# HOME_AUTOMATION.net
KiCad netlist of a schematic drawn in EAGLE
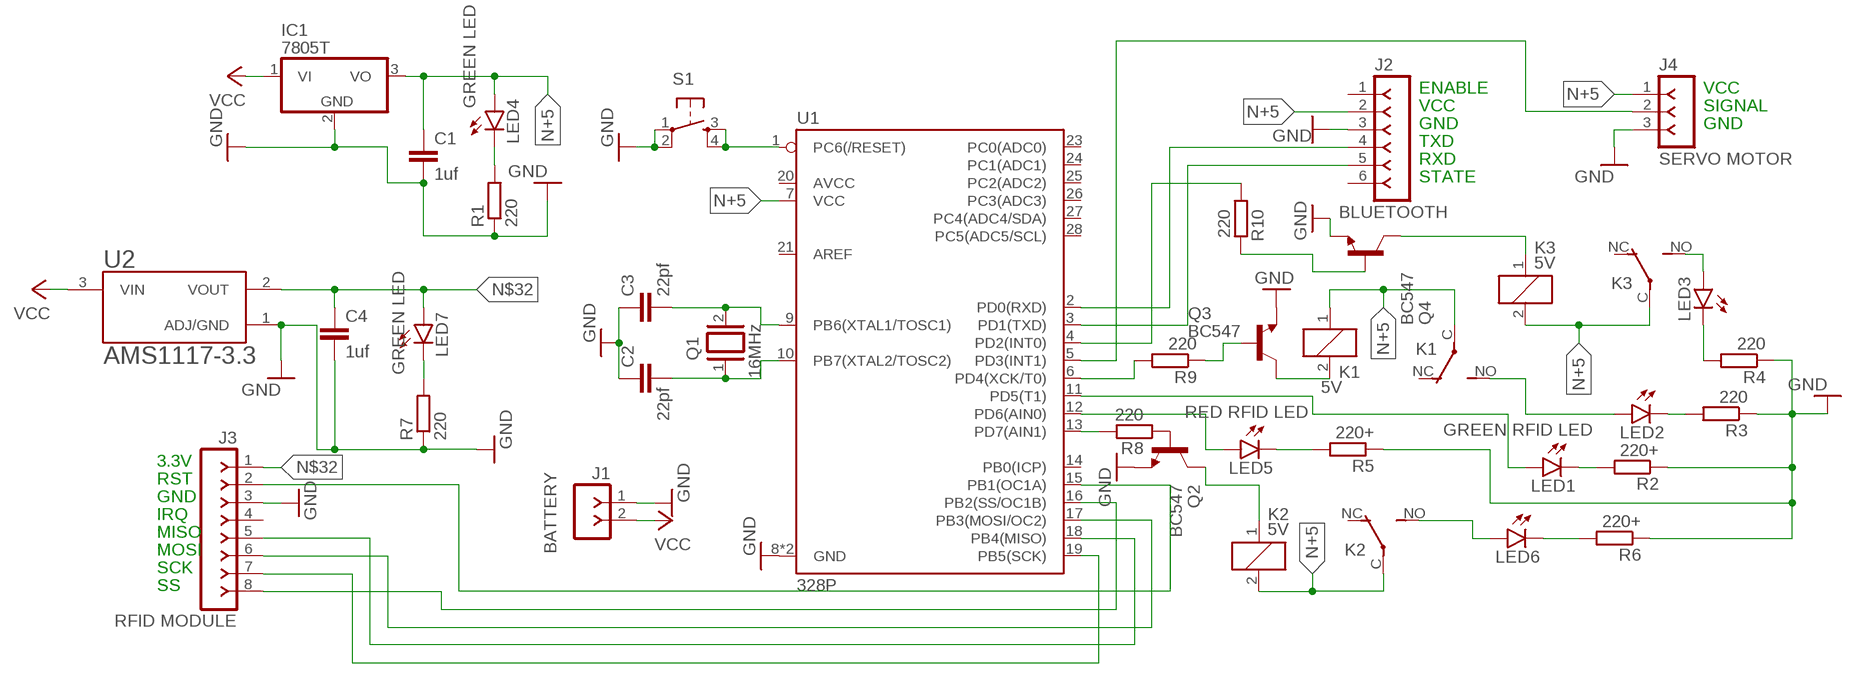
[diagram p0: schematic, sheet 1]

(export (version "E")
  (design (tool "Eeschema 10.0.6"))
  (components
    (comp (ref "C1")
      (value "1uf")
      (footprint "eagle-import:C025-025X050")
      (libsource (lib "eagle-import") (part "C-EU025-025X050"))
    )
    (comp (ref "C2")
      (value "22pf")
      (footprint "eagle-import:C025-025X050")
      (libsource (lib "eagle-import") (part "C-EU025-025X050"))
    )
    (comp (ref "C3")
      (value "22pf")
      (footprint "eagle-import:C025-025X050")
      (libsource (lib "eagle-import") (part "C-EU025-025X050"))
    )
    (comp (ref "C4")
      (value "1uf")
      (footprint "eagle-import:C025-025X050")
      (libsource (lib "eagle-import") (part "C-EU025-025X050"))
    )
    (comp (ref "IC1")
      (value "7805T")
      (footprint "eagle-import:TO220H")
      (libsource (lib "eagle-import") (part "78T05"))
    )
    (comp (ref "J1")
      (value "BATTERY")
      (footprint "eagle-import:SIP-100-02-32Y")
      (libsource (lib "eagle-import") (part "F-1X02-SIP-100-32Y"))
    )
    (comp (ref "J2")
      (value "BLUETOOTH")
      (footprint "eagle-import:SIP-100-06-32Y")
      (libsource (lib "eagle-import") (part "F-1X06-SIP-100-32Y"))
    )
    (comp (ref "J3")
      (value "RFID MODULE")
      (footprint "eagle-import:SIP-100-08-32Y")
      (libsource (lib "eagle-import") (part "F-1X08-SIP-100-32Y"))
    )
    (comp (ref "J4")
      (value "SERVO MOTOR")
      (footprint "eagle-import:SIP-100-03-32Y")
      (libsource (lib "eagle-import") (part "F-1X03-SIP-100-32Y"))
    )
    (comp (ref "K1")
      (value "5V")
      (footprint "eagle-import:CQ1")
      (libsource (lib "eagle-import") (part "CQ1-12V"))
    )
    (comp (ref "K2")
      (value "5V")
      (footprint "eagle-import:CQ1")
      (libsource (lib "eagle-import") (part "CQ1-12V"))
    )
    (comp (ref "K3")
      (value "5V")
      (footprint "eagle-import:CQ1")
      (libsource (lib "eagle-import") (part "CQ1-12V"))
    )
    (comp (ref "LED1")
      (value "GREEN RFID LED")
      (footprint "eagle-import:LED5MM")
      (libsource (lib "eagle-import") (part "LED5MM"))
    )
    (comp (ref "LED2")
      (value "LED5MM")
      (footprint "eagle-import:LED5MM")
      (libsource (lib "eagle-import") (part "LED5MM"))
    )
    (comp (ref "LED3")
      (value "LED5MM")
      (footprint "eagle-import:LED5MM")
      (libsource (lib "eagle-import") (part "LED5MM"))
    )
    (comp (ref "LED4")
      (value "GREEN LED")
      (footprint "eagle-import:LED5MM")
      (libsource (lib "eagle-import") (part "LED5MM"))
    )
    (comp (ref "LED5")
      (value "RED RFID LED")
      (footprint "eagle-import:LED5MM")
      (libsource (lib "eagle-import") (part "LED5MM"))
    )
    (comp (ref "LED6")
      (value "LED5MM")
      (footprint "eagle-import:LED5MM")
      (libsource (lib "eagle-import") (part "LED5MM"))
    )
    (comp (ref "LED7")
      (value "GREEN LED")
      (footprint "eagle-import:LED5MM")
      (libsource (lib "eagle-import") (part "LED5MM"))
    )
    (comp (ref "Q1")
      (value "16MHz")
      (footprint "eagle-import:QS")
      (libsource (lib "eagle-import") (part "XTAL/S"))
    )
    (comp (ref "Q2")
      (value "BC547")
      (footprint "eagle-import:TO92")
      (libsource (lib "eagle-import") (part "BC547"))
    )
    (comp (ref "Q3")
      (value "BC547")
      (footprint "eagle-import:TO92")
      (libsource (lib "eagle-import") (part "BC547"))
    )
    (comp (ref "Q4")
      (value "BC547")
      (footprint "eagle-import:TO92")
      (libsource (lib "eagle-import") (part "BC547"))
    )
    (comp (ref "R1")
      (value "220")
      (footprint "eagle-import:0204_7")
      (libsource (lib "eagle-import") (part "R-EU_0204/7"))
    )
    (comp (ref "R2")
      (value "220+")
      (footprint "eagle-import:0204_7")
      (libsource (lib "eagle-import") (part "R-EU_0204/7"))
    )
    (comp (ref "R3")
      (value "220")
      (footprint "eagle-import:0204_7")
      (libsource (lib "eagle-import") (part "R-EU_0204/7"))
    )
    (comp (ref "R4")
      (value "220")
      (footprint "eagle-import:0204_7")
      (libsource (lib "eagle-import") (part "R-EU_0204/7"))
    )
    (comp (ref "R5")
      (value "220+")
      (footprint "eagle-import:0204_7")
      (libsource (lib "eagle-import") (part "R-EU_0204/7"))
    )
    (comp (ref "R6")
      (value "220+")
      (footprint "eagle-import:0204_7")
      (libsource (lib "eagle-import") (part "R-EU_0204/7"))
    )
    (comp (ref "R7")
      (value "220")
      (footprint "eagle-import:0204_7")
      (libsource (lib "eagle-import") (part "R-EU_0204/7"))
    )
    (comp (ref "R8")
      (value "220")
      (footprint "eagle-import:0204_7")
      (libsource (lib "eagle-import") (part "R-EU_0204/7"))
    )
    (comp (ref "R9")
      (value "220")
      (footprint "eagle-import:0204_7")
      (libsource (lib "eagle-import") (part "R-EU_0204/7"))
    )
    (comp (ref "R10")
      (value "220")
      (footprint "eagle-import:0204_7")
      (libsource (lib "eagle-import") (part "R-EU_0204/7"))
    )
    (comp (ref "S1")
      (value "TAC_SWITCHPTH")
      (footprint "eagle-import:TACTILE-PTH")
      (libsource (lib "eagle-import") (part "TAC_SWITCHPTH"))
    )
    (comp (ref "U1")
      (value "328P")
      (footprint "eagle-import:DIP28")
      (libsource (lib "eagle-import") (part "ATMEGA328P_PDIP"))
    )
    (comp (ref "U2")
      (value "AMS1117-3.3")
      (footprint "eagle-import:SOT229P700X180-4N")
      (fields (field (name "MF") "Advanced Monolithic Systems"))
      (libsource (lib "eagle-import") (part "AMS1117-3.3"))
    )
  )
  (nets
    (net (code "1") (name "GND") (class "Default")
      (node (ref "C1") (pin "2") (pinfunction "2_2") (pintype "passive"))
      (node (ref "C2") (pin "1") (pinfunction "1_1") (pintype "passive"))
      (node (ref "C3") (pin "1") (pinfunction "1_1") (pintype "passive"))
      (node (ref "C4") (pin "2") (pinfunction "2_2") (pintype "passive"))
      (node (ref "IC1") (pin "2") (pinfunction "GND_2") (pintype "passive"))
      (node (ref "J1") (pin "1") (pinfunction "1_1") (pintype "passive"))
      (node (ref "J2") (pin "3") (pinfunction "3_3") (pintype "passive"))
      (node (ref "J3") (pin "3") (pinfunction "3_3") (pintype "passive"))
      (node (ref "J4") (pin "3") (pinfunction "3_3") (pintype "passive"))
      (node (ref "Q2") (pin "1") (pinfunction "E_1") (pintype "passive"))
      (node (ref "Q3") (pin "1") (pinfunction "E_1") (pintype "passive"))
      (node (ref "Q4") (pin "1") (pinfunction "E_1") (pintype "passive"))
      (node (ref "R1") (pin "1") (pinfunction "1_1") (pintype "passive"))
      (node (ref "R2") (pin "1") (pinfunction "1_1") (pintype "passive"))
      (node (ref "R3") (pin "1") (pinfunction "1_1") (pintype "passive"))
      (node (ref "R4") (pin "1") (pinfunction "1_1") (pintype "passive"))
      (node (ref "R5") (pin "1") (pinfunction "1_1") (pintype "passive"))
      (node (ref "R6") (pin "1") (pinfunction "1_1") (pintype "passive"))
      (node (ref "R7") (pin "1") (pinfunction "1_1") (pintype "passive"))
      (node (ref "S1") (pin "1") (pinfunction "1_1") (pintype "passive"))
      (node (ref "S1") (pin "2") (pinfunction "2_2") (pintype "passive"))
      (node (ref "U1") (pin "22") (pinfunction "GND_22") (pintype "bidirectional"))
      (node (ref "U1") (pin "8") (pinfunction "GND_8") (pintype "bidirectional"))
      (node (ref "U2") (pin "1") (pinfunction "ADJ/GND_1") (pintype "power_in"))
    )
    (net (code "2") (name "N$32") (class "Default")
      (node (ref "C4") (pin "1") (pinfunction "1_1") (pintype "passive"))
      (node (ref "LED7") (pin "A") (pinfunction "A_A") (pintype "passive"))
      (node (ref "U2") (pin "2") (pinfunction "VOUT_2") (pintype "output"))
    )
    (net (code "3") (name "N+5") (class "Default")
      (node (ref "C1") (pin "1") (pinfunction "1_1") (pintype "passive"))
      (node (ref "IC1") (pin "3") (pinfunction "VO_3") (pintype "passive"))
      (node (ref "LED4") (pin "A") (pinfunction "A_A") (pintype "passive"))
    )
    (net (code "4") (name "Net-(K1B-P)") (class "Default")
      (node (ref "K1") (pin "1") (pinfunction "1_1") (pintype "passive"))
      (node (ref "K1") (pin "C") (pinfunction "P_C") (pintype "passive"))
    )
    (net (code "5") (name "Net-(K1B-S)") (class "Default")
      (node (ref "K1") (pin "NO") (pinfunction "S_NO") (pintype "passive"))
      (node (ref "LED2") (pin "A") (pinfunction "A_A") (pintype "passive"))
    )
    (net (code "6") (name "Net-(K2B-P)") (class "Default")
      (node (ref "K2") (pin "2") (pinfunction "2_2") (pintype "passive"))
      (node (ref "K2") (pin "C") (pinfunction "P_C") (pintype "passive"))
    )
    (net (code "7") (name "Net-(K2B-S)") (class "Default")
      (node (ref "K2") (pin "NO") (pinfunction "S_NO") (pintype "passive"))
      (node (ref "LED6") (pin "A") (pinfunction "A_A") (pintype "passive"))
    )
    (net (code "8") (name "Net-(K3B-P)") (class "Default")
      (node (ref "K3") (pin "2") (pinfunction "2_2") (pintype "passive"))
      (node (ref "K3") (pin "C") (pinfunction "P_C") (pintype "passive"))
    )
    (net (code "9") (name "Net-(K3B-S)") (class "Default")
      (node (ref "K3") (pin "NO") (pinfunction "S_NO") (pintype "passive"))
      (node (ref "LED3") (pin "A") (pinfunction "A_A") (pintype "passive"))
    )
    (net (code "10") (name "Net-(LED1-C)") (class "Default")
      (node (ref "LED1") (pin "K") (pinfunction "C_K") (pintype "passive"))
      (node (ref "R2") (pin "2") (pinfunction "2_2") (pintype "passive"))
    )
    (net (code "11") (name "Net-(LED2-C)") (class "Default")
      (node (ref "LED2") (pin "K") (pinfunction "C_K") (pintype "passive"))
      (node (ref "R3") (pin "2") (pinfunction "2_2") (pintype "passive"))
    )
    (net (code "12") (name "Net-(LED3-C)") (class "Default")
      (node (ref "LED3") (pin "K") (pinfunction "C_K") (pintype "passive"))
      (node (ref "R4") (pin "2") (pinfunction "2_2") (pintype "passive"))
    )
    (net (code "13") (name "Net-(LED4-C)") (class "Default")
      (node (ref "LED4") (pin "K") (pinfunction "C_K") (pintype "passive"))
      (node (ref "R1") (pin "2") (pinfunction "2_2") (pintype "passive"))
    )
    (net (code "14") (name "Net-(LED5-C)") (class "Default")
      (node (ref "LED5") (pin "K") (pinfunction "C_K") (pintype "passive"))
      (node (ref "R5") (pin "2") (pinfunction "2_2") (pintype "passive"))
    )
    (net (code "15") (name "Net-(LED6-C)") (class "Default")
      (node (ref "LED6") (pin "K") (pinfunction "C_K") (pintype "passive"))
      (node (ref "R6") (pin "2") (pinfunction "2_2") (pintype "passive"))
    )
    (net (code "16") (name "Net-(LED7-C)") (class "Default")
      (node (ref "LED7") (pin "K") (pinfunction "C_K") (pintype "passive"))
      (node (ref "R7") (pin "2") (pinfunction "2_2") (pintype "passive"))
    )
    (net (code "17") (name "Net-(Q2-B)") (class "Default")
      (node (ref "Q2") (pin "2") (pinfunction "B_2") (pintype "passive"))
      (node (ref "R8") (pin "1") (pinfunction "1_1") (pintype "passive"))
    )
    (net (code "18") (name "Net-(Q2-C)") (class "Default")
      (node (ref "K2") (pin "1") (pinfunction "1_1") (pintype "passive"))
      (node (ref "Q2") (pin "3") (pinfunction "C_3") (pintype "passive"))
    )
    (net (code "19") (name "Net-(Q3-B)") (class "Default")
      (node (ref "Q3") (pin "2") (pinfunction "B_2") (pintype "passive"))
      (node (ref "R9") (pin "1") (pinfunction "1_1") (pintype "passive"))
    )
    (net (code "20") (name "Net-(Q3-C)") (class "Default")
      (node (ref "K1") (pin "2") (pinfunction "2_2") (pintype "passive"))
      (node (ref "Q3") (pin "3") (pinfunction "C_3") (pintype "passive"))
    )
    (net (code "21") (name "Net-(Q4-B)") (class "Default")
      (node (ref "Q4") (pin "2") (pinfunction "B_2") (pintype "passive"))
      (node (ref "R10") (pin "2") (pinfunction "2_2") (pintype "passive"))
    )
    (net (code "22") (name "Net-(Q4-C)") (class "Default")
      (node (ref "K3") (pin "1") (pinfunction "1_1") (pintype "passive"))
      (node (ref "Q4") (pin "3") (pinfunction "C_3") (pintype "passive"))
    )
    (net (code "23") (name "Net-(U1-PB1(OC1A))") (class "Default")
      (node (ref "J3") (pin "2") (pinfunction "2_2") (pintype "passive"))
      (node (ref "U1") (pin "15") (pinfunction "PB1(OC1A)_15") (pintype "bidirectional"))
    )
    (net (code "24") (name "Net-(U1-PB2(SS{slash}OC1B))") (class "Default")
      (node (ref "J3") (pin "8") (pinfunction "8_8") (pintype "passive"))
      (node (ref "U1") (pin "16") (pinfunction "PB2(SS/OC1B)_16") (pintype "bidirectional"))
    )
    (net (code "25") (name "Net-(U1-PB3(MOSI{slash}OC2))") (class "Default")
      (node (ref "J3") (pin "6") (pinfunction "6_6") (pintype "passive"))
      (node (ref "U1") (pin "17") (pinfunction "PB3(MOSI/OC2)_17") (pintype "bidirectional"))
    )
    (net (code "26") (name "Net-(U1-PB4(MISO))") (class "Default")
      (node (ref "J3") (pin "5") (pinfunction "5_5") (pintype "passive"))
      (node (ref "U1") (pin "18") (pinfunction "PB4(MISO)_18") (pintype "bidirectional"))
    )
    (net (code "27") (name "Net-(U1-PB5(SCK))") (class "Default")
      (node (ref "J3") (pin "7") (pinfunction "7_7") (pintype "passive"))
      (node (ref "U1") (pin "19") (pinfunction "PB5(SCK)_19") (pintype "bidirectional"))
    )
    (net (code "28") (name "Net-(U1-PB6(XTAL1{slash}TOSC1))") (class "Default")
      (node (ref "C3") (pin "2") (pinfunction "2_2") (pintype "passive"))
      (node (ref "Q1") (pin "2") (pinfunction "2_2") (pintype "passive"))
      (node (ref "U1") (pin "9") (pinfunction "PB6(XTAL1/TOSC1)_9") (pintype "bidirectional"))
    )
    (net (code "29") (name "Net-(U1-PB7(XTAL2{slash}TOSC2))") (class "Default")
      (node (ref "C2") (pin "2") (pinfunction "2_2") (pintype "passive"))
      (node (ref "Q1") (pin "1") (pinfunction "1_1") (pintype "passive"))
      (node (ref "U1") (pin "10") (pinfunction "PB7(XTAL2/TOSC2)_10") (pintype "bidirectional"))
    )
    (net (code "30") (name "Net-(U1-PC6({slash}RESET))") (class "Default")
      (node (ref "S1") (pin "3") (pinfunction "3_3") (pintype "passive"))
      (node (ref "S1") (pin "4") (pinfunction "4_4") (pintype "passive"))
      (node (ref "U1") (pin "1") (pinfunction "PC6(/RESET)_1") (pintype "bidirectional"))
    )
    (net (code "31") (name "Net-(U1-PD0(RXD))") (class "Default")
      (node (ref "J2") (pin "4") (pinfunction "4_4") (pintype "passive"))
      (node (ref "U1") (pin "2") (pinfunction "PD0(RXD)_2") (pintype "bidirectional"))
    )
    (net (code "32") (name "Net-(U1-PD1(TXD))") (class "Default")
      (node (ref "J2") (pin "5") (pinfunction "5_5") (pintype "passive"))
      (node (ref "U1") (pin "3") (pinfunction "PD1(TXD)_3") (pintype "bidirectional"))
    )
    (net (code "33") (name "Net-(U1-PD2(INT0))") (class "Default")
      (node (ref "R10") (pin "1") (pinfunction "1_1") (pintype "passive"))
      (node (ref "U1") (pin "4") (pinfunction "PD2(INT0)_4") (pintype "bidirectional"))
    )
    (net (code "34") (name "Net-(U1-PD3(INT1))") (class "Default")
      (node (ref "J4") (pin "2") (pinfunction "2_2") (pintype "passive"))
      (node (ref "U1") (pin "5") (pinfunction "PD3(INT1)_5") (pintype "bidirectional"))
    )
    (net (code "35") (name "Net-(U1-PD4(XCK{slash}T0))") (class "Default")
      (node (ref "R9") (pin "2") (pinfunction "2_2") (pintype "passive"))
      (node (ref "U1") (pin "6") (pinfunction "PD4(XCK/T0)_6") (pintype "bidirectional"))
    )
    (net (code "36") (name "Net-(U1-PD5(T1))") (class "Default")
      (node (ref "LED1") (pin "A") (pinfunction "A_A") (pintype "passive"))
      (node (ref "U1") (pin "11") (pinfunction "PD5(T1)_11") (pintype "bidirectional"))
    )
    (net (code "37") (name "Net-(U1-PD6(AIN0))") (class "Default")
      (node (ref "LED5") (pin "A") (pinfunction "A_A") (pintype "passive"))
      (node (ref "U1") (pin "12") (pinfunction "PD6(AIN0)_12") (pintype "bidirectional"))
    )
    (net (code "38") (name "Net-(U1-PD7(AIN1))") (class "Default")
      (node (ref "R8") (pin "2") (pinfunction "2_2") (pintype "passive"))
      (node (ref "U1") (pin "13") (pinfunction "PD7(AIN1)_13") (pintype "bidirectional"))
    )
    (net (code "39") (name "VCC") (class "Default")
      (node (ref "IC1") (pin "1") (pinfunction "VI_1") (pintype "input"))
      (node (ref "J1") (pin "2") (pinfunction "2_2") (pintype "passive"))
      (node (ref "U2") (pin "3") (pinfunction "VIN_3") (pintype "input"))
    )
    (net (code "40") (name "unconnected-(J2-Pad1)") (class "Default")
      (node (ref "J2") (pin "1") (pinfunction "1_1") (pintype "passive"))
    )
    (net (code "41") (name "unconnected-(J2-Pad2)") (class "Default")
      (node (ref "J2") (pin "2") (pinfunction "2_2") (pintype "passive"))
    )
    (net (code "42") (name "unconnected-(J2-Pad6)") (class "Default")
      (node (ref "J2") (pin "6") (pinfunction "6_6") (pintype "passive"))
    )
    (net (code "43") (name "unconnected-(J3-Pad1)") (class "Default")
      (node (ref "J3") (pin "1") (pinfunction "1_1") (pintype "passive"))
    )
    (net (code "44") (name "unconnected-(J3-Pad4)") (class "Default")
      (node (ref "J3") (pin "4") (pinfunction "4_4") (pintype "passive"))
    )
    (net (code "45") (name "unconnected-(J4-Pad1)") (class "Default")
      (node (ref "J4") (pin "1") (pinfunction "1_1") (pintype "passive"))
    )
    (net (code "46") (name "unconnected-(K1B-O-PadNC)") (class "Default")
      (node (ref "K1") (pin "NC") (pinfunction "O_NC") (pintype "passive"))
    )
    (net (code "47") (name "unconnected-(K2B-O-PadNC)") (class "Default")
      (node (ref "K2") (pin "NC") (pinfunction "O_NC") (pintype "passive"))
    )
    (net (code "48") (name "unconnected-(K3B-O-PadNC)") (class "Default")
      (node (ref "K3") (pin "NC") (pinfunction "O_NC") (pintype "passive"))
    )
    (net (code "49") (name "unconnected-(U1-AREF-Pad21)") (class "Default")
      (node (ref "U1") (pin "21") (pinfunction "AREF_21") (pintype "bidirectional"))
    )
    (net (code "50") (name "unconnected-(U1-AVCC-Pad20)") (class "Default")
      (node (ref "U1") (pin "20") (pinfunction "AVCC_20") (pintype "bidirectional"))
    )
    (net (code "51") (name "unconnected-(U1-PB0(ICP)-Pad14)") (class "Default")
      (node (ref "U1") (pin "14") (pinfunction "PB0(ICP)_14") (pintype "bidirectional"))
    )
    (net (code "52") (name "unconnected-(U1-PC0(ADC0)-Pad23)") (class "Default")
      (node (ref "U1") (pin "23") (pinfunction "PC0(ADC0)_23") (pintype "bidirectional"))
    )
    (net (code "53") (name "unconnected-(U1-PC1(ADC1)-Pad24)") (class "Default")
      (node (ref "U1") (pin "24") (pinfunction "PC1(ADC1)_24") (pintype "bidirectional"))
    )
    (net (code "54") (name "unconnected-(U1-PC2(ADC2)-Pad25)") (class "Default")
      (node (ref "U1") (pin "25") (pinfunction "PC2(ADC2)_25") (pintype "bidirectional"))
    )
    (net (code "55") (name "unconnected-(U1-PC3(ADC3)-Pad26)") (class "Default")
      (node (ref "U1") (pin "26") (pinfunction "PC3(ADC3)_26") (pintype "bidirectional"))
    )
    (net (code "56") (name "unconnected-(U1-PC4(ADC4{slash}SDA)-Pad27)") (class "Default")
      (node (ref "U1") (pin "27") (pinfunction "PC4(ADC4/SDA)_27") (pintype "bidirectional"))
    )
    (net (code "57") (name "unconnected-(U1-PC5(ADC5{slash}SCL)-Pad28)") (class "Default")
      (node (ref "U1") (pin "28") (pinfunction "PC5(ADC5/SCL)_28") (pintype "bidirectional"))
    )
    (net (code "58") (name "unconnected-(U1-VCC-Pad7)") (class "Default")
      (node (ref "U1") (pin "7") (pinfunction "VCC_7") (pintype "bidirectional"))
    )
  )
)
